# design.net
KiCad netlist of a schematic drawn in EAGLE
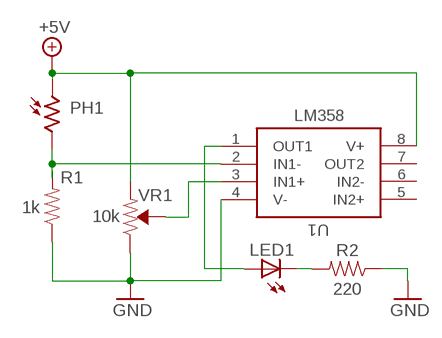
[diagram p0: schematic, sheet 1]

(export (version "E")
  (design (tool "Eeschema 10.0.6"))
  (components
    (comp (ref "LED1")
      (value "LED")
      (footprint "eagle-import:SMARTLED-TTW")
      (libsource (lib "eagle-import") (part "LED"))
    )
    (comp (ref "PH1")
      (value "D1160_12")
      (footprint "eagle-import:D11XX")
      (libsource (lib "eagle-import") (part "D1160_12"))
    )
    (comp (ref "R1")
      (value "1k")
      (footprint "eagle-import:AXIAL-0.3")
      (libsource (lib "eagle-import") (part "10MOHM-HORIZ-1/4W-5%"))
    )
    (comp (ref "R2")
      (value "220")
      (footprint "eagle-import:AXIAL-0.3")
      (libsource (lib "eagle-import") (part "10MOHM-HORIZ-1/4W-5%"))
    )
    (comp (ref "U1")
      (value "LM358")
      (footprint "eagle-import:LM358DR")
      (fields
        (field (name "DIGIKEY_PART_NUMBER") "296-1014-1-ND")
        (field (name "MANUFACTURER") "Texas Instruments")
        (field (name "MPN") "LM358DR")
        (field (name "MPN_1") "LM358")
        (field (name "CREATED_BY") "PCBLayout.com")
      )
      (libsource (lib "eagle-import") (part "LM358DR"))
    )
    (comp (ref "VR1")
      (value "10k")
      (footprint "eagle-import:TRIMPOT-PTH-3386U")
      (libsource (lib "eagle-import") (part "TRIMPOT-PTH-10MM-KNOB-1/2W-10%"))
    )
  )
  (nets
    (net (code "1") (name "+5V") (class "Default")
      (node (ref "PH1") (pin "1") (pinfunction "1_1") (pintype "passive"))
      (node (ref "U1") (pin "8") (pinfunction "V+_8") (pintype "power_in"))
      (node (ref "VR1") (pin "1") (pinfunction "CCW_1") (pintype "passive"))
    )
    (net (code "2") (name "GND") (class "Default")
      (node (ref "R1") (pin "P$1") (pinfunction "1_P$1") (pintype "passive"))
      (node (ref "R2") (pin "P$1") (pinfunction "1_P$1") (pintype "passive"))
      (node (ref "U1") (pin "4") (pinfunction "V-_4") (pintype "power_in"))
      (node (ref "VR1") (pin "3") (pinfunction "CW_3") (pintype "passive"))
    )
    (net (code "3") (name "Net-(LED1-A)") (class "Default")
      (node (ref "LED1") (pin "A@1") (pinfunction "A_A@1") (pintype "passive"))
      (node (ref "U1") (pin "1") (pinfunction "OUT1_1") (pintype "output"))
    )
    (net (code "4") (name "Net-(LED1-C)") (class "Default")
      (node (ref "LED1") (pin "C@1") (pinfunction "C_C@1") (pintype "passive"))
      (node (ref "R2") (pin "P$2") (pinfunction "2_P$2") (pintype "passive"))
    )
    (net (code "5") (name "Net-(R1-2)") (class "Default")
      (node (ref "PH1") (pin "2") (pinfunction "2_2") (pintype "passive"))
      (node (ref "R1") (pin "P$2") (pinfunction "2_P$2") (pintype "passive"))
      (node (ref "U1") (pin "2") (pinfunction "IN1-_2") (pintype "input"))
    )
    (net (code "6") (name "Net-(U1-IN1+)") (class "Default")
      (node (ref "U1") (pin "3") (pinfunction "IN1+_3") (pintype "input"))
      (node (ref "VR1") (pin "2") (pinfunction "WIPER_2") (pintype "passive"))
    )
    (net (code "7") (name "unconnected-(U1-IN2+-Pad5)") (class "Default")
      (node (ref "U1") (pin "5") (pinfunction "IN2+_5") (pintype "input"))
    )
    (net (code "8") (name "unconnected-(U1-IN2--Pad6)") (class "Default")
      (node (ref "U1") (pin "6") (pinfunction "IN2-_6") (pintype "input"))
    )
    (net (code "9") (name "unconnected-(U1-OUT2-Pad7)") (class "Default")
      (node (ref "U1") (pin "7") (pinfunction "OUT2_7") (pintype "output"))
    )
  )
)
